# GSR.net
KiCad netlist of a schematic drawn in EAGLE
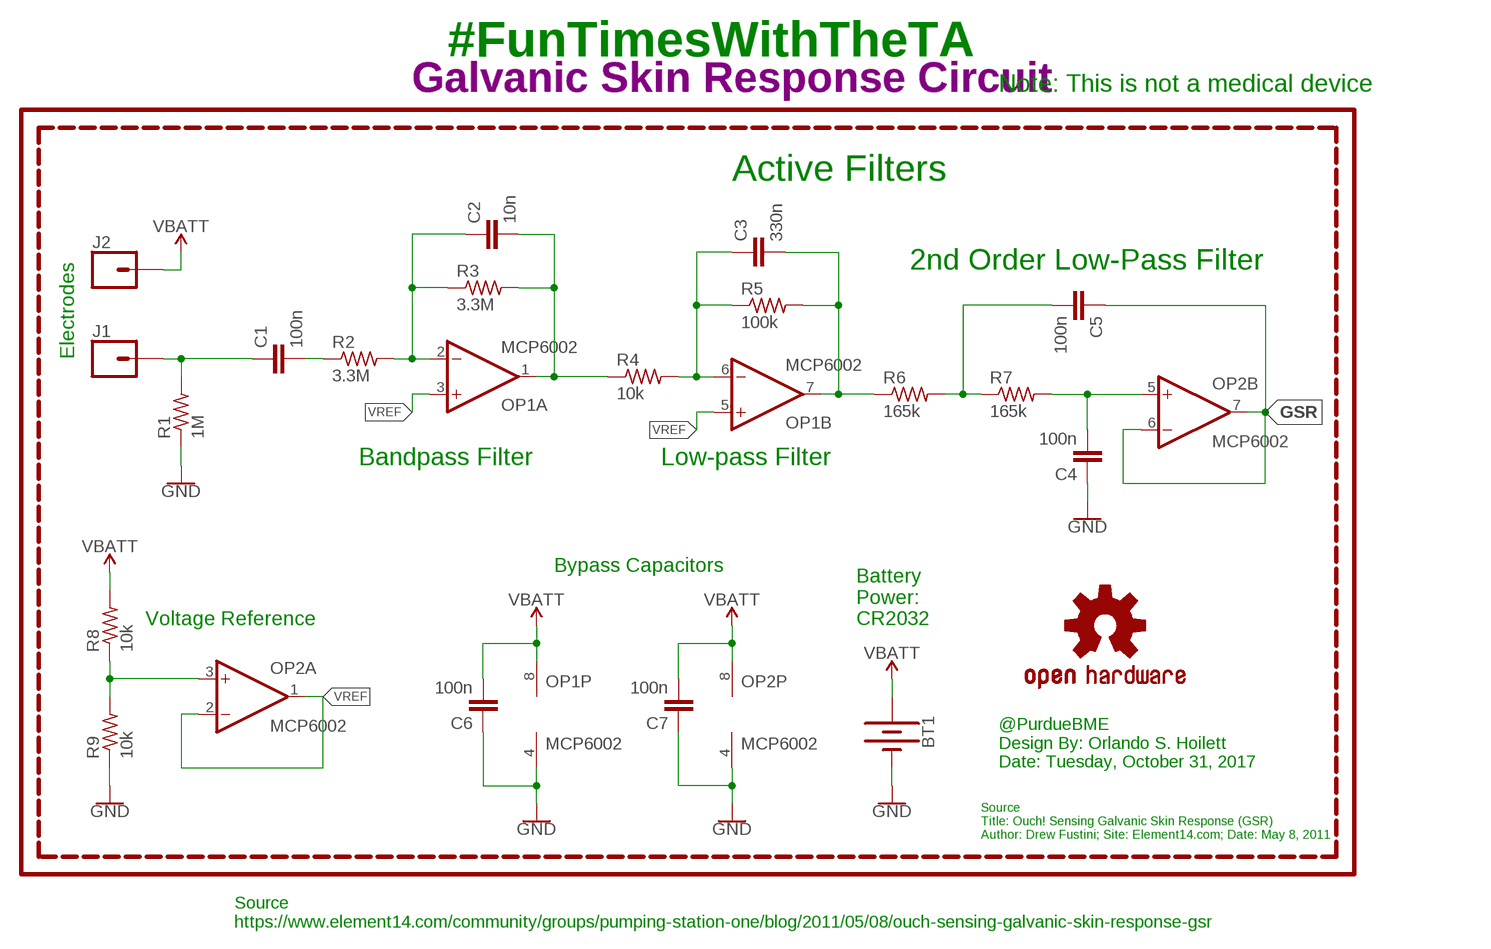
[diagram p0: schematic, sheet 1]

(export (version "E")
  (design (tool "Eeschema 10.0.6"))
  (components
    (comp (ref "BT1")
      (value "BATTERY-20MM_SMD_4LEGS_OVERPASTE")
      (footprint "eagle-import:BATTCON_20MM_4LEGS_OVERPASTE")
      (libsource (lib "eagle-import") (part "BATTERY-20MM_SMD_4LEGS_OVERPASTE"))
    )
    (comp (ref "C1")
      (value "100n")
      (footprint "eagle-import:C0402")
      (libsource (lib "eagle-import") (part "CAPACITOR0402"))
    )
    (comp (ref "C2")
      (value "10n")
      (footprint "eagle-import:C0402")
      (libsource (lib "eagle-import") (part "CAPACITOR0402"))
    )
    (comp (ref "C3")
      (value "330n")
      (footprint "eagle-import:C0402")
      (libsource (lib "eagle-import") (part "CAPACITOR0402"))
    )
    (comp (ref "C4")
      (value "100n")
      (footprint "eagle-import:C0402")
      (libsource (lib "eagle-import") (part "CAPACITOR0402"))
    )
    (comp (ref "C5")
      (value "100n")
      (footprint "eagle-import:C0402")
      (libsource (lib "eagle-import") (part "CAPACITOR0402"))
    )
    (comp (ref "C6")
      (value "100n")
      (footprint "eagle-import:C0402")
      (libsource (lib "eagle-import") (part "CAPACITOR0402"))
    )
    (comp (ref "C7")
      (value "100n")
      (footprint "eagle-import:C0402")
      (libsource (lib "eagle-import") (part "CAPACITOR0402"))
    )
    (comp (ref "J1")
      (value "CONN_01")
      (footprint "eagle-import:1X01")
      (libsource (lib "eagle-import") (part "CONN_01"))
    )
    (comp (ref "J2")
      (value "CONN_01")
      (footprint "eagle-import:1X01")
      (libsource (lib "eagle-import") (part "CONN_01"))
    )
    (comp (ref "LOGO1")
      (value "OSHW-LOGOM")
      (footprint "eagle-import:OSHW-LOGO-M")
      (libsource (lib "eagle-import") (part "OSHW-LOGOM"))
    )
    (comp (ref "OP1")
      (value "MCP6002")
      (footprint "eagle-import:MSOP08")
      (fields (field (name "MF") "ALTERA CORPORATION") (field (name "MPN") "AD8607ARMZ-REEL"))
      (libsource (lib "eagle-import") (part "OP-DUALRM"))
    )
    (comp (ref "OP2")
      (value "MCP6002")
      (footprint "eagle-import:MSOP08")
      (fields (field (name "MF") "ALTERA CORPORATION") (field (name "MPN") "AD8607ARMZ-REEL"))
      (libsource (lib "eagle-import") (part "OP-DUALRM"))
    )
    (comp (ref "R1")
      (value "1M")
      (footprint "eagle-import:R0402")
      (libsource (lib "eagle-import") (part "RESISTOR0402"))
    )
    (comp (ref "R2")
      (value "3.3M")
      (footprint "eagle-import:R0402")
      (libsource (lib "eagle-import") (part "RESISTOR0402"))
    )
    (comp (ref "R3")
      (value "3.3M")
      (footprint "eagle-import:R0402")
      (libsource (lib "eagle-import") (part "RESISTOR0402"))
    )
    (comp (ref "R4")
      (value "10k")
      (footprint "eagle-import:R0402")
      (libsource (lib "eagle-import") (part "RESISTOR0402"))
    )
    (comp (ref "R5")
      (value "100k")
      (footprint "eagle-import:R0402")
      (libsource (lib "eagle-import") (part "RESISTOR0402"))
    )
    (comp (ref "R6")
      (value "165k")
      (footprint "eagle-import:R0402")
      (libsource (lib "eagle-import") (part "RESISTOR0402"))
    )
    (comp (ref "R7")
      (value "165k")
      (footprint "eagle-import:R0402")
      (libsource (lib "eagle-import") (part "RESISTOR0402"))
    )
    (comp (ref "R8")
      (value "10k")
      (footprint "eagle-import:R0402")
      (libsource (lib "eagle-import") (part "RESISTOR0402"))
    )
    (comp (ref "R9")
      (value "10k")
      (footprint "eagle-import:R0402")
      (libsource (lib "eagle-import") (part "RESISTOR0402"))
    )
  )
  (nets
    (net (code "1") (name "GND") (class "Default")
      (node (ref "BT1") (pin "2") (pinfunction "-_2") (pintype "power_in"))
      (node (ref "C4") (pin "1") (pinfunction "1_1") (pintype "passive"))
      (node (ref "C6") (pin "1") (pinfunction "1_1") (pintype "passive"))
      (node (ref "C7") (pin "1") (pinfunction "1_1") (pintype "passive"))
      (node (ref "OP1") (pin "4") (pinfunction "V-_4") (pintype "power_in"))
      (node (ref "OP2") (pin "4") (pinfunction "V-_4") (pintype "power_in"))
      (node (ref "R1") (pin "1") (pinfunction "1_1") (pintype "passive"))
      (node (ref "R9") (pin "1") (pinfunction "1_1") (pintype "passive"))
    )
    (net (code "2") (name "GSR") (class "Default")
      (node (ref "C5") (pin "1") (pinfunction "1_1") (pintype "passive"))
      (node (ref "OP2") (pin "6") (pinfunction "-IN_6") (pintype "input"))
      (node (ref "OP2") (pin "7") (pinfunction "OUT_7") (pintype "output"))
    )
    (net (code "3") (name "Net-(C1-Pad1)") (class "Default")
      (node (ref "C1") (pin "1") (pinfunction "1_1") (pintype "passive"))
      (node (ref "J1") (pin "1") (pinfunction "1_1") (pintype "passive"))
      (node (ref "R1") (pin "2") (pinfunction "2_2") (pintype "passive"))
    )
    (net (code "4") (name "Net-(C1-Pad2)") (class "Default")
      (node (ref "C1") (pin "2") (pinfunction "2_2") (pintype "passive"))
      (node (ref "R2") (pin "1") (pinfunction "1_1") (pintype "passive"))
    )
    (net (code "5") (name "Net-(C5-Pad2)") (class "Default")
      (node (ref "C5") (pin "2") (pinfunction "2_2") (pintype "passive"))
      (node (ref "R6") (pin "2") (pinfunction "2_2") (pintype "passive"))
      (node (ref "R7") (pin "1") (pinfunction "1_1") (pintype "passive"))
    )
    (net (code "6") (name "Net-(OP1A--IN)") (class "Default")
      (node (ref "C2") (pin "1") (pinfunction "1_1") (pintype "passive"))
      (node (ref "OP1") (pin "2") (pinfunction "-IN_2") (pintype "input"))
      (node (ref "R2") (pin "2") (pinfunction "2_2") (pintype "passive"))
      (node (ref "R3") (pin "1") (pinfunction "1_1") (pintype "passive"))
    )
    (net (code "7") (name "Net-(OP1A-OUT)") (class "Default")
      (node (ref "C2") (pin "2") (pinfunction "2_2") (pintype "passive"))
      (node (ref "OP1") (pin "1") (pinfunction "OUT_1") (pintype "output"))
      (node (ref "R3") (pin "2") (pinfunction "2_2") (pintype "passive"))
      (node (ref "R4") (pin "1") (pinfunction "1_1") (pintype "passive"))
    )
    (net (code "8") (name "Net-(OP1B--IN)") (class "Default")
      (node (ref "C3") (pin "1") (pinfunction "1_1") (pintype "passive"))
      (node (ref "OP1") (pin "6") (pinfunction "-IN_6") (pintype "input"))
      (node (ref "R4") (pin "2") (pinfunction "2_2") (pintype "passive"))
      (node (ref "R5") (pin "1") (pinfunction "1_1") (pintype "passive"))
    )
    (net (code "9") (name "Net-(OP1B-OUT)") (class "Default")
      (node (ref "C3") (pin "2") (pinfunction "2_2") (pintype "passive"))
      (node (ref "OP1") (pin "7") (pinfunction "OUT_7") (pintype "output"))
      (node (ref "R5") (pin "2") (pinfunction "2_2") (pintype "passive"))
      (node (ref "R6") (pin "1") (pinfunction "1_1") (pintype "passive"))
    )
    (net (code "10") (name "Net-(OP2A-+IN)") (class "Default")
      (node (ref "OP2") (pin "3") (pinfunction "+IN_3") (pintype "input"))
      (node (ref "R8") (pin "1") (pinfunction "1_1") (pintype "passive"))
      (node (ref "R9") (pin "2") (pinfunction "2_2") (pintype "passive"))
    )
    (net (code "11") (name "Net-(OP2B-+IN)") (class "Default")
      (node (ref "C4") (pin "2") (pinfunction "2_2") (pintype "passive"))
      (node (ref "OP2") (pin "5") (pinfunction "+IN_5") (pintype "input"))
      (node (ref "R7") (pin "2") (pinfunction "2_2") (pintype "passive"))
    )
    (net (code "12") (name "VBATT") (class "Default")
      (node (ref "BT1") (pin "1") (pinfunction "+_1") (pintype "power_in"))
      (node (ref "C6") (pin "2") (pinfunction "2_2") (pintype "passive"))
      (node (ref "C7") (pin "2") (pinfunction "2_2") (pintype "passive"))
      (node (ref "J2") (pin "1") (pinfunction "1_1") (pintype "passive"))
      (node (ref "OP1") (pin "8") (pinfunction "V+_8") (pintype "power_in"))
      (node (ref "OP2") (pin "8") (pinfunction "V+_8") (pintype "power_in"))
      (node (ref "R8") (pin "2") (pinfunction "2_2") (pintype "passive"))
    )
    (net (code "13") (name "VREF") (class "Default")
      (node (ref "OP1") (pin "3") (pinfunction "+IN_3") (pintype "input"))
      (node (ref "OP1") (pin "5") (pinfunction "+IN_5") (pintype "input"))
      (node (ref "OP2") (pin "1") (pinfunction "OUT_1") (pintype "output"))
      (node (ref "OP2") (pin "2") (pinfunction "-IN_2") (pintype "input"))
    )
  )
)
